# MotorShield.net
KiCad netlist of a schematic drawn in EAGLE
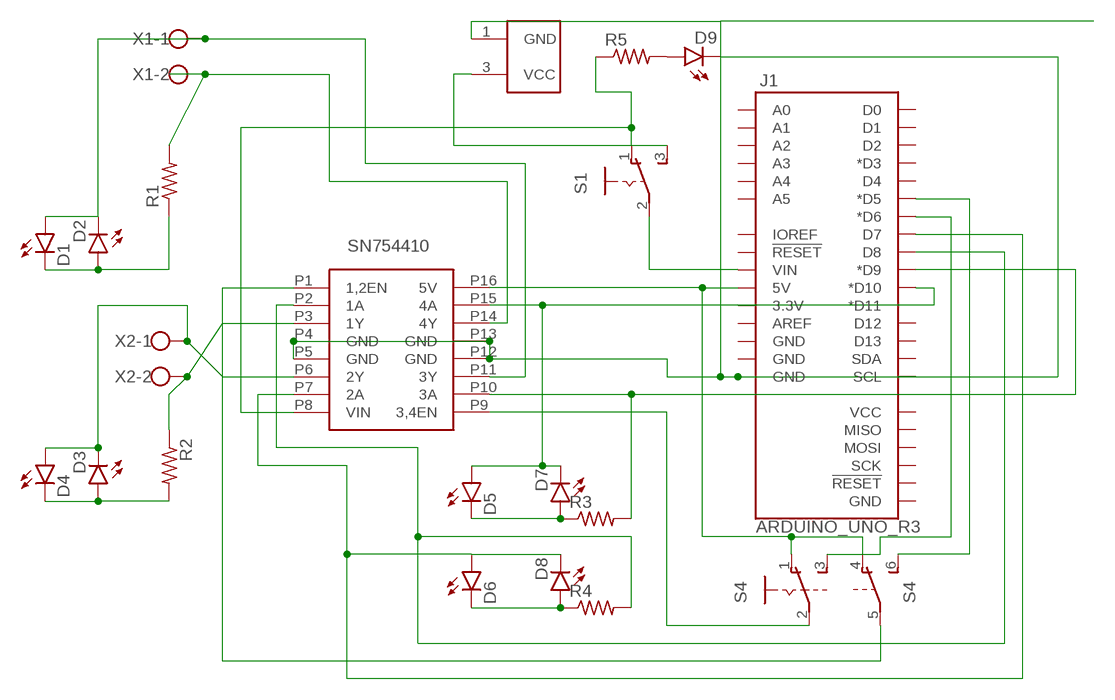
[diagram p0: schematic, sheet 1]

(export (version "E")
  (design (tool "Eeschema 10.0.6"))
  (components
    (comp (ref "D1")
      (value "LED3MM")
      (footprint "eagle-import:LED3MM")
      (libsource (lib "eagle-import") (part "LED3MM"))
    )
    (comp (ref "D2")
      (value "LED3MM")
      (footprint "eagle-import:LED3MM")
      (libsource (lib "eagle-import") (part "LED3MM"))
    )
    (comp (ref "D3")
      (value "LED3MM")
      (footprint "eagle-import:LED3MM")
      (libsource (lib "eagle-import") (part "LED3MM"))
    )
    (comp (ref "D4")
      (value "LED3MM")
      (footprint "eagle-import:LED3MM")
      (libsource (lib "eagle-import") (part "LED3MM"))
    )
    (comp (ref "D5")
      (value "LED3MM")
      (footprint "eagle-import:LED3MM")
      (libsource (lib "eagle-import") (part "LED3MM"))
    )
    (comp (ref "D6")
      (value "LED3MM")
      (footprint "eagle-import:LED3MM")
      (libsource (lib "eagle-import") (part "LED3MM"))
    )
    (comp (ref "D7")
      (value "LED3MM")
      (footprint "eagle-import:LED3MM")
      (libsource (lib "eagle-import") (part "LED3MM"))
    )
    (comp (ref "D8")
      (value "LED3MM")
      (footprint "eagle-import:LED3MM")
      (libsource (lib "eagle-import") (part "LED3MM"))
    )
    (comp (ref "D9")
      (value "LED3MM")
      (footprint "eagle-import:LED3MM")
      (libsource (lib "eagle-import") (part "LED3MM"))
    )
    (comp (ref "J1")
      (value "ARDUINO_UNO_R3")
      (footprint "eagle-import:ARDUINO_R3")
      (libsource (lib "eagle-import") (part "ARDUINO_UNO_R3"))
    )
    (comp (ref "R1")
      (value "RESISTOR0204/7")
      (footprint "eagle-import:0204_7")
      (libsource (lib "eagle-import") (part "RESISTOR0204/7"))
    )
    (comp (ref "R2")
      (value "RESISTOR0204/7")
      (footprint "eagle-import:0204_7")
      (libsource (lib "eagle-import") (part "RESISTOR0204/7"))
    )
    (comp (ref "R3")
      (value "RESISTOR0204/7")
      (footprint "eagle-import:0204_7")
      (libsource (lib "eagle-import") (part "RESISTOR0204/7"))
    )
    (comp (ref "R4")
      (value "RESISTOR0204/7")
      (footprint "eagle-import:0204_7")
      (libsource (lib "eagle-import") (part "RESISTOR0204/7"))
    )
    (comp (ref "R5")
      (value "RESISTOR0204/7")
      (footprint "eagle-import:0204_7")
      (libsource (lib "eagle-import") (part "RESISTOR0204/7"))
    )
    (comp (ref "S1")
      (value "SLIDE_SWITCH")
      (footprint "eagle-import:SLIDE_SWITCH")
      (libsource (lib "eagle-import") (part "SLIDE_SWITCH"))
    )
    (comp (ref "S4")
      (value "DUAL_SLIDE_SWITCH")
      (footprint "eagle-import:DUAL_SLIDE_SWITCH")
      (libsource (lib "eagle-import") (part "DUAL_SLIDE_SWITCH"))
    )
    (comp (ref "U$1")
      (value "MOTOR_DRIVERDIP16")
      (footprint "eagle-import:DIP16")
      (libsource (lib "eagle-import") (part "MOTOR_DRIVERDIP16"))
    )
    (comp (ref "U$2")
      (value "BARREL_CONNECTOR")
      (footprint "eagle-import:5.5-2.5-BARRELCONNECTOR")
      (libsource (lib "eagle-import") (part "BARREL_CONNECTOR"))
    )
    (comp (ref "X1")
      (value "SCREWCONNECTOR")
      (footprint "eagle-import:2PIN-SCREW-TERMINAL")
      (fields (field (name "MPN") "237-102"))
      (libsource (lib "eagle-import") (part "SCREWCONNECTOR"))
    )
    (comp (ref "X2")
      (value "SCREWCONNECTOR")
      (footprint "eagle-import:2PIN-SCREW-TERMINAL")
      (fields (field (name "MPN") "237-102"))
      (libsource (lib "eagle-import") (part "SCREWCONNECTOR"))
    )
  )
  (nets
    (net (code "1") (name "Net-(D1-C)") (class "Default")
      (node (ref "D1") (pin "K") (pinfunction "C_K") (pintype "passive"))
      (node (ref "D2") (pin "A") (pinfunction "A_A") (pintype "passive"))
      (node (ref "R1") (pin "1") (pinfunction "1_1") (pintype "passive"))
    )
    (net (code "2") (name "Net-(D2-C)") (class "Default")
      (node (ref "D1") (pin "A") (pinfunction "A_A") (pintype "passive"))
      (node (ref "D2") (pin "K") (pinfunction "C_K") (pintype "passive"))
      (node (ref "U$1") (pin "P11") (pinfunction "3Y_P11") (pintype "output"))
      (node (ref "X1") (pin "1") (pinfunction "KL_1") (pintype "passive"))
    )
    (net (code "3") (name "Net-(D3-C)") (class "Default")
      (node (ref "D3") (pin "K") (pinfunction "C_K") (pintype "passive"))
      (node (ref "D4") (pin "A") (pinfunction "A_A") (pintype "passive"))
      (node (ref "U$1") (pin "P6") (pinfunction "2Y_P6") (pintype "output"))
      (node (ref "X2") (pin "1") (pinfunction "KL_1") (pintype "passive"))
    )
    (net (code "4") (name "Net-(D4-C)") (class "Default")
      (node (ref "D3") (pin "A") (pinfunction "A_A") (pintype "passive"))
      (node (ref "D4") (pin "K") (pinfunction "C_K") (pintype "passive"))
      (node (ref "R2") (pin "2") (pinfunction "2_2") (pintype "passive"))
    )
    (net (code "5") (name "Net-(D5-C)") (class "Default")
      (node (ref "D5") (pin "K") (pinfunction "C_K") (pintype "passive"))
      (node (ref "D7") (pin "A") (pinfunction "A_A") (pintype "passive"))
      (node (ref "R3") (pin "1") (pinfunction "1_1") (pintype "passive"))
    )
    (net (code "6") (name "Net-(D6-C)") (class "Default")
      (node (ref "D6") (pin "K") (pinfunction "C_K") (pintype "passive"))
      (node (ref "D8") (pin "A") (pinfunction "A_A") (pintype "passive"))
      (node (ref "R4") (pin "1") (pinfunction "1_1") (pintype "passive"))
    )
    (net (code "7") (name "Net-(D7-C)") (class "Default")
      (node (ref "D5") (pin "A") (pinfunction "A_A") (pintype "passive"))
      (node (ref "D7") (pin "K") (pinfunction "C_K") (pintype "passive"))
      (node (ref "J1") (pin "D10") (pinfunction "*D10_D10") (pintype "bidirectional"))
      (node (ref "U$1") (pin "P15") (pinfunction "4A_P15") (pintype "input"))
    )
    (net (code "8") (name "Net-(D8-C)") (class "Default")
      (node (ref "D6") (pin "A") (pinfunction "A_A") (pintype "passive"))
      (node (ref "D8") (pin "K") (pinfunction "C_K") (pintype "passive"))
      (node (ref "J1") (pin "D7") (pinfunction "D7_D7") (pintype "bidirectional"))
      (node (ref "U$1") (pin "P7") (pinfunction "2A_P7") (pintype "input"))
    )
    (net (code "9") (name "Net-(D9-C)") (class "Default")
      (node (ref "D9") (pin "K") (pinfunction "C_K") (pintype "passive"))
      (node (ref "J1") (pin "GND@2") (pinfunction "GND_GND@2") (pintype "bidirectional"))
      (node (ref "U$1") (pin "P12") (pinfunction "GND_P12") (pintype "power_in"))
      (node (ref "U$1") (pin "P13") (pinfunction "GND_P13") (pintype "power_in"))
      (node (ref "U$1") (pin "P4") (pinfunction "GND_P4") (pintype "power_in"))
      (node (ref "U$1") (pin "P5") (pinfunction "GND_P5") (pintype "power_in"))
      (node (ref "U$2") (pin "1") (pinfunction "GND_1") (pintype "bidirectional"))
    )
    (net (code "10") (name "Net-(D9-PadA)") (class "Default")
      (node (ref "D9") (pin "A") (pinfunction "A_A") (pintype "passive"))
      (node (ref "R5") (pin "2") (pinfunction "2_2") (pintype "passive"))
    )
    (net (code "11") (name "Net-(J1-*D5)") (class "Default")
      (node (ref "J1") (pin "D5") (pinfunction "*D5_D5") (pintype "bidirectional"))
      (node (ref "S4") (pin "6") (pinfunction "S_6") (pintype "passive"))
    )
    (net (code "12") (name "Net-(J1-*D6)") (class "Default")
      (node (ref "J1") (pin "D6") (pinfunction "*D6_D6") (pintype "bidirectional"))
      (node (ref "S4") (pin "3") (pinfunction "S_3") (pintype "passive"))
    )
    (net (code "13") (name "Net-(J1-*D9)") (class "Default")
      (node (ref "J1") (pin "D9") (pinfunction "*D9_D9") (pintype "bidirectional"))
      (node (ref "R3") (pin "2") (pinfunction "2_2") (pintype "passive"))
      (node (ref "U$1") (pin "P10") (pinfunction "3A_P10") (pintype "input"))
    )
    (net (code "14") (name "Net-(S1-O)") (class "Default")
      (node (ref "R5") (pin "1") (pinfunction "1_1") (pintype "passive"))
      (node (ref "S1") (pin "1") (pinfunction "O_1") (pintype "passive"))
      (node (ref "U$1") (pin "P8") (pinfunction "VIN_P8") (pintype "power_in"))
    )
    (net (code "15") (name "Net-(S1-P)") (class "Default")
      (node (ref "J1") (pin "VIN") (pinfunction "VIN_VIN") (pintype "bidirectional"))
      (node (ref "S1") (pin "2") (pinfunction "P_2") (pintype "passive"))
    )
    (net (code "16") (name "Net-(S1-S)") (class "Default")
      (node (ref "S1") (pin "3") (pinfunction "S_3") (pintype "passive"))
      (node (ref "U$2") (pin "3") (pinfunction "VCC_3") (pintype "bidirectional"))
    )
    (net (code "17") (name "Net-(S4A-O)") (class "Default")
      (node (ref "J1") (pin "5V") (pinfunction "5V_5V") (pintype "bidirectional"))
      (node (ref "S4") (pin "1") (pinfunction "O_1") (pintype "passive"))
      (node (ref "S4") (pin "4") (pinfunction "O_4") (pintype "passive"))
      (node (ref "U$1") (pin "P16") (pinfunction "5V_P16") (pintype "power_in"))
    )
    (net (code "18") (name "Net-(S4A-P)") (class "Default")
      (node (ref "S4") (pin "2") (pinfunction "P_2") (pintype "passive"))
      (node (ref "U$1") (pin "P9") (pinfunction "3,4EN_P9") (pintype "input"))
    )
    (net (code "19") (name "Net-(S4B-P)") (class "Default")
      (node (ref "S4") (pin "5") (pinfunction "P_5") (pintype "passive"))
      (node (ref "U$1") (pin "P1") (pinfunction "1,2EN_P1") (pintype "input"))
    )
    (net (code "20") (name "Net-(U$1-1A)") (class "Default")
      (node (ref "J1") (pin "D8") (pinfunction "D8_D8") (pintype "bidirectional"))
      (node (ref "R4") (pin "2") (pinfunction "2_2") (pintype "passive"))
      (node (ref "U$1") (pin "P2") (pinfunction "1A_P2") (pintype "input"))
    )
    (net (code "21") (name "Net-(U$1-1Y)") (class "Default")
      (node (ref "R2") (pin "1") (pinfunction "1_1") (pintype "passive"))
      (node (ref "U$1") (pin "P3") (pinfunction "1Y_P3") (pintype "output"))
      (node (ref "X2") (pin "2") (pinfunction "KL_2") (pintype "passive"))
    )
    (net (code "22") (name "Net-(U$1-4Y)") (class "Default")
      (node (ref "R1") (pin "2") (pinfunction "2_2") (pintype "passive"))
      (node (ref "U$1") (pin "P14") (pinfunction "4Y_P14") (pintype "output"))
      (node (ref "X1") (pin "2") (pinfunction "KL_2") (pintype "passive"))
    )
    (net (code "23") (name "unconnected-(J1-*D3-PadD3)") (class "Default")
      (node (ref "J1") (pin "D3") (pinfunction "*D3_D3") (pintype "bidirectional"))
    )
    (net (code "24") (name "unconnected-(J1-*D11-PadD11)") (class "Default")
      (node (ref "J1") (pin "D11") (pinfunction "*D11_D11") (pintype "bidirectional"))
    )
    (net (code "25") (name "unconnected-(J1-GND-PadGND@1)") (class "Default")
      (node (ref "J1") (pin "GND@1") (pinfunction "GND_GND@1") (pintype "bidirectional"))
    )
    (net (code "26") (name "unconnected-(J1-GND-PadGND@3)") (class "Default")
      (node (ref "J1") (pin "GND@3") (pinfunction "GND_GND@3") (pintype "bidirectional"))
    )
    (net (code "27") (name "unconnected-(J1-GND-PadGND@4)") (class "Default")
      (node (ref "J1") (pin "GND@4") (pinfunction "GND_GND@4") (pintype "bidirectional"))
    )
    (net (code "28") (name "unconnected-(J1-Pad3.3V)") (class "Default")
      (node (ref "J1") (pin "3.3V") (pinfunction "3.3V_3.3V") (pintype "bidirectional"))
    )
    (net (code "29") (name "unconnected-(J1-PadA0)") (class "Default")
      (node (ref "J1") (pin "A0") (pinfunction "A0_A0") (pintype "bidirectional"))
    )
    (net (code "30") (name "unconnected-(J1-PadA1)") (class "Default")
      (node (ref "J1") (pin "A1") (pinfunction "A1_A1") (pintype "bidirectional"))
    )
    (net (code "31") (name "unconnected-(J1-PadA2)") (class "Default")
      (node (ref "J1") (pin "A2") (pinfunction "A2_A2") (pintype "bidirectional"))
    )
    (net (code "32") (name "unconnected-(J1-PadA3)") (class "Default")
      (node (ref "J1") (pin "A3") (pinfunction "A3_A3") (pintype "bidirectional"))
    )
    (net (code "33") (name "unconnected-(J1-PadA4)") (class "Default")
      (node (ref "J1") (pin "A4") (pinfunction "A4_A4") (pintype "bidirectional"))
    )
    (net (code "34") (name "unconnected-(J1-PadA5)") (class "Default")
      (node (ref "J1") (pin "A5") (pinfunction "A5_A5") (pintype "bidirectional"))
    )
    (net (code "35") (name "unconnected-(J1-PadAREF)") (class "Default")
      (node (ref "J1") (pin "AREF") (pinfunction "AREF_AREF") (pintype "bidirectional"))
    )
    (net (code "36") (name "unconnected-(J1-PadD0)") (class "Default")
      (node (ref "J1") (pin "D0") (pinfunction "D0_D0") (pintype "bidirectional"))
    )
    (net (code "37") (name "unconnected-(J1-PadD1)") (class "Default")
      (node (ref "J1") (pin "D1") (pinfunction "D1_D1") (pintype "bidirectional"))
    )
    (net (code "38") (name "unconnected-(J1-PadD2)") (class "Default")
      (node (ref "J1") (pin "D2") (pinfunction "D2_D2") (pintype "bidirectional"))
    )
    (net (code "39") (name "unconnected-(J1-PadD4)") (class "Default")
      (node (ref "J1") (pin "D4") (pinfunction "D4_D4") (pintype "bidirectional"))
    )
    (net (code "40") (name "unconnected-(J1-PadD12)") (class "Default")
      (node (ref "J1") (pin "D12") (pinfunction "D12_D12") (pintype "bidirectional"))
    )
    (net (code "41") (name "unconnected-(J1-PadD13)") (class "Default")
      (node (ref "J1") (pin "D13") (pinfunction "D13_D13") (pintype "bidirectional"))
    )
    (net (code "42") (name "unconnected-(J1-PadIOREF)") (class "Default")
      (node (ref "J1") (pin "IOREF") (pinfunction "IOREF_IOREF") (pintype "bidirectional"))
    )
    (net (code "43") (name "unconnected-(J1-PadMISO)") (class "Default")
      (node (ref "J1") (pin "MISO") (pinfunction "MISO_MISO") (pintype "bidirectional"))
    )
    (net (code "44") (name "unconnected-(J1-PadMOSI)") (class "Default")
      (node (ref "J1") (pin "MOSI") (pinfunction "MOSI_MOSI") (pintype "bidirectional"))
    )
    (net (code "45") (name "unconnected-(J1-PadSCK)") (class "Default")
      (node (ref "J1") (pin "SCK") (pinfunction "SCK_SCK") (pintype "bidirectional"))
    )
    (net (code "46") (name "unconnected-(J1-PadSCL)") (class "Default")
      (node (ref "J1") (pin "SCL") (pinfunction "SCL_SCL") (pintype "bidirectional"))
    )
    (net (code "47") (name "unconnected-(J1-PadSDA)") (class "Default")
      (node (ref "J1") (pin "SDA") (pinfunction "SDA_SDA") (pintype "bidirectional"))
    )
    (net (code "48") (name "unconnected-(J1-PadVCC)") (class "Default")
      (node (ref "J1") (pin "VCC") (pinfunction "VCC_VCC") (pintype "bidirectional"))
    )
    (net (code "49") (name "unconnected-(J1-~{RESET}-PadRESET@1)") (class "Default")
      (node (ref "J1") (pin "RESET@1") (pinfunction "~{RESET}_RESET@1") (pintype "bidirectional"))
    )
    (net (code "50") (name "unconnected-(J1-~{RESET}-PadRESET@2)") (class "Default")
      (node (ref "J1") (pin "RESET@2") (pinfunction "~{RESET}_RESET@2") (pintype "bidirectional"))
    )
  )
)
